# 17_PM8916_LDO.net
KiCad netlist of a schematic drawn in Altium Designer
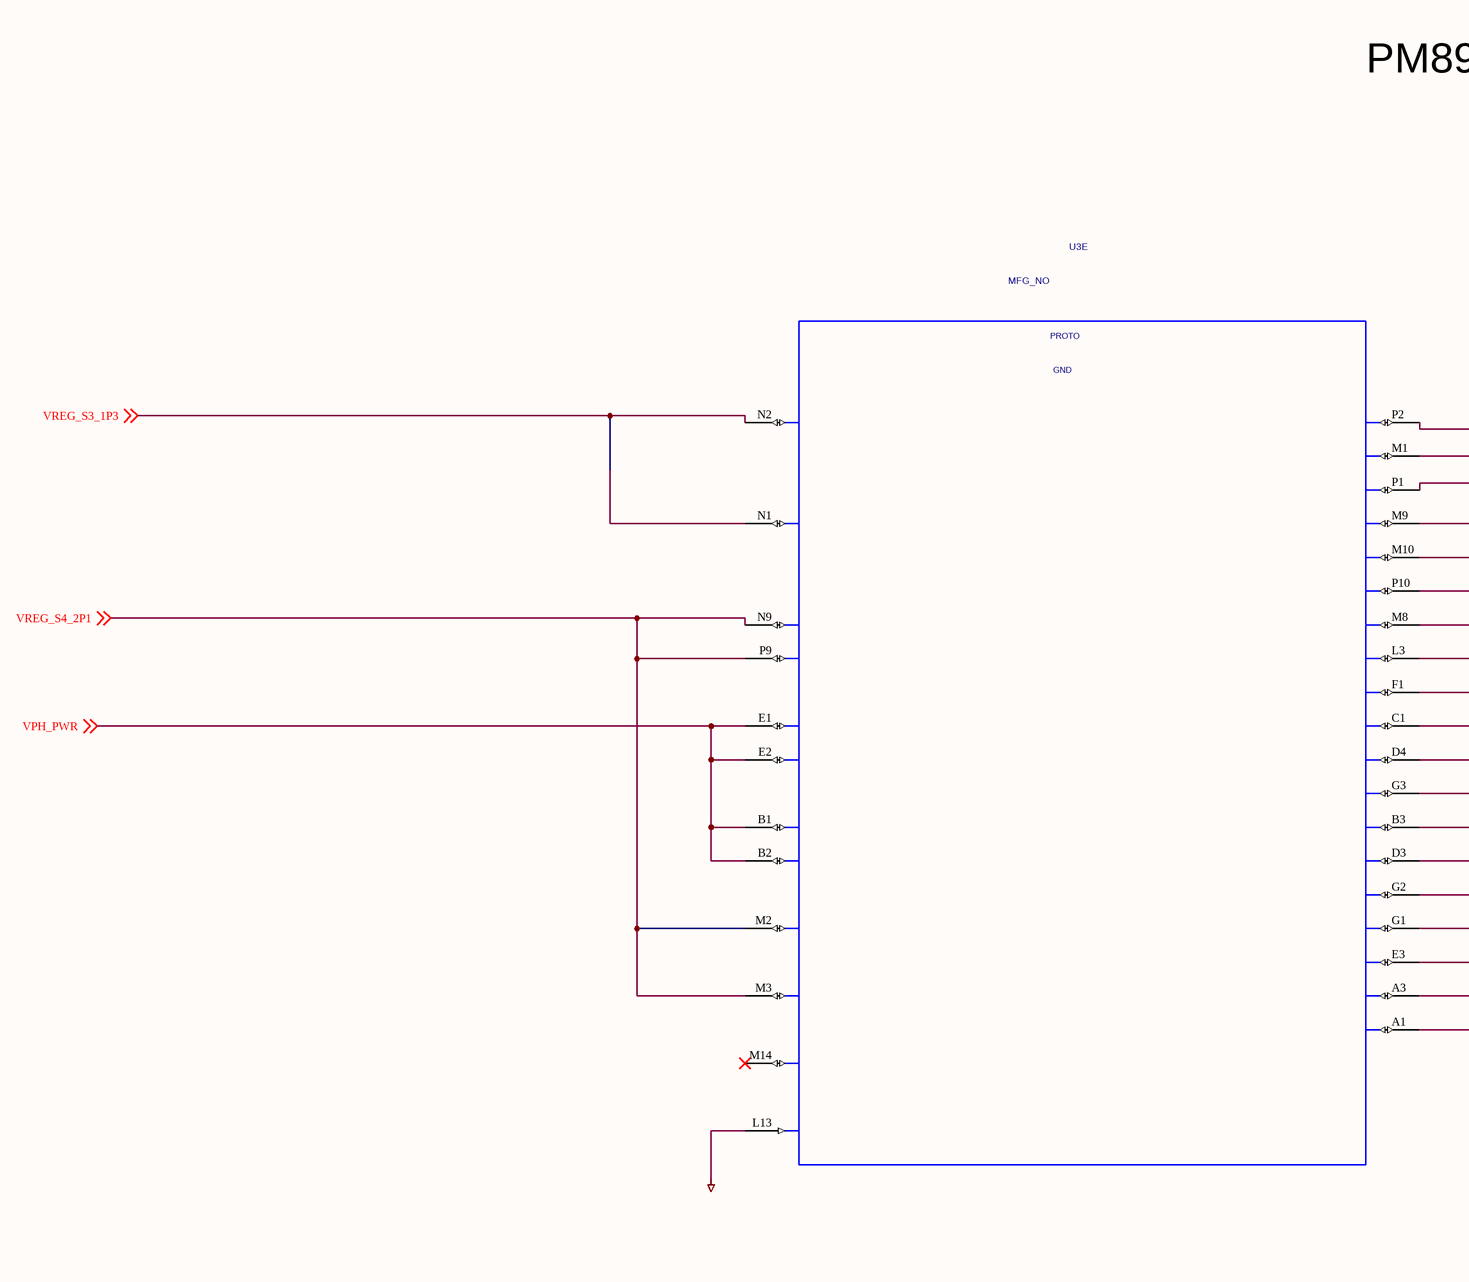
[diagram p0: 17 PM8916_LDO.SchDoc, top left]
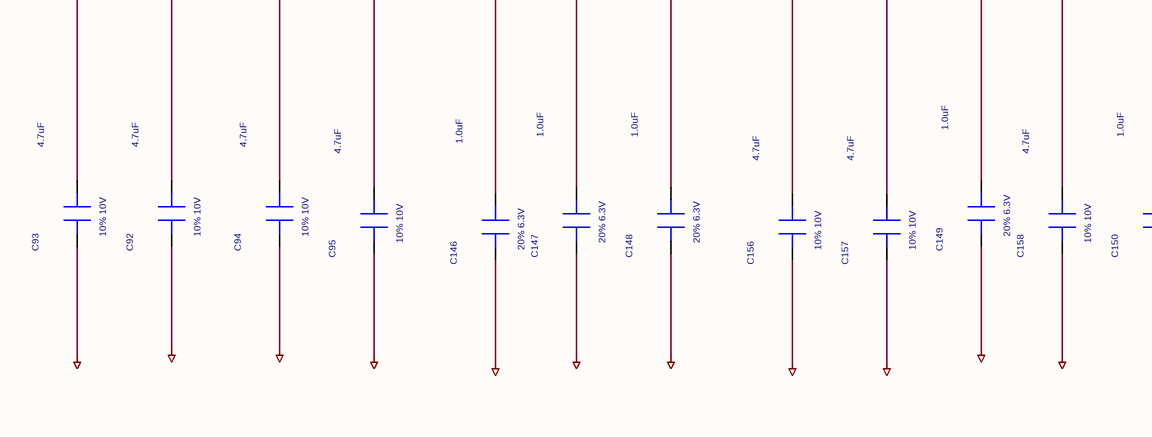
[diagram p1: 17 PM8916_LDO.SchDoc, top middle]
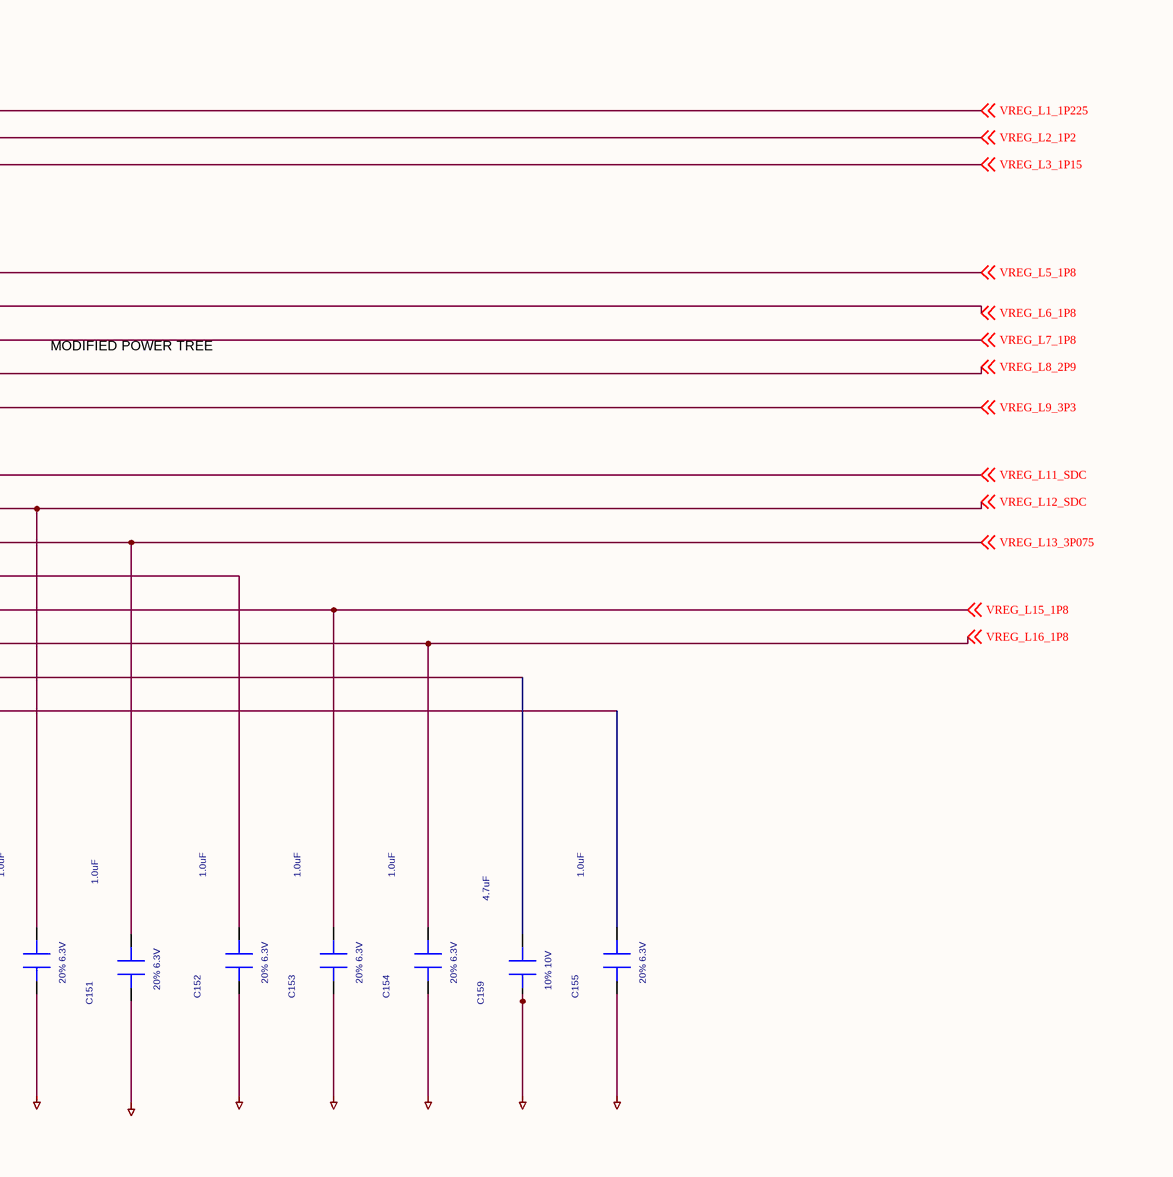
[diagram p2: 17 PM8916_LDO.SchDoc, top right]
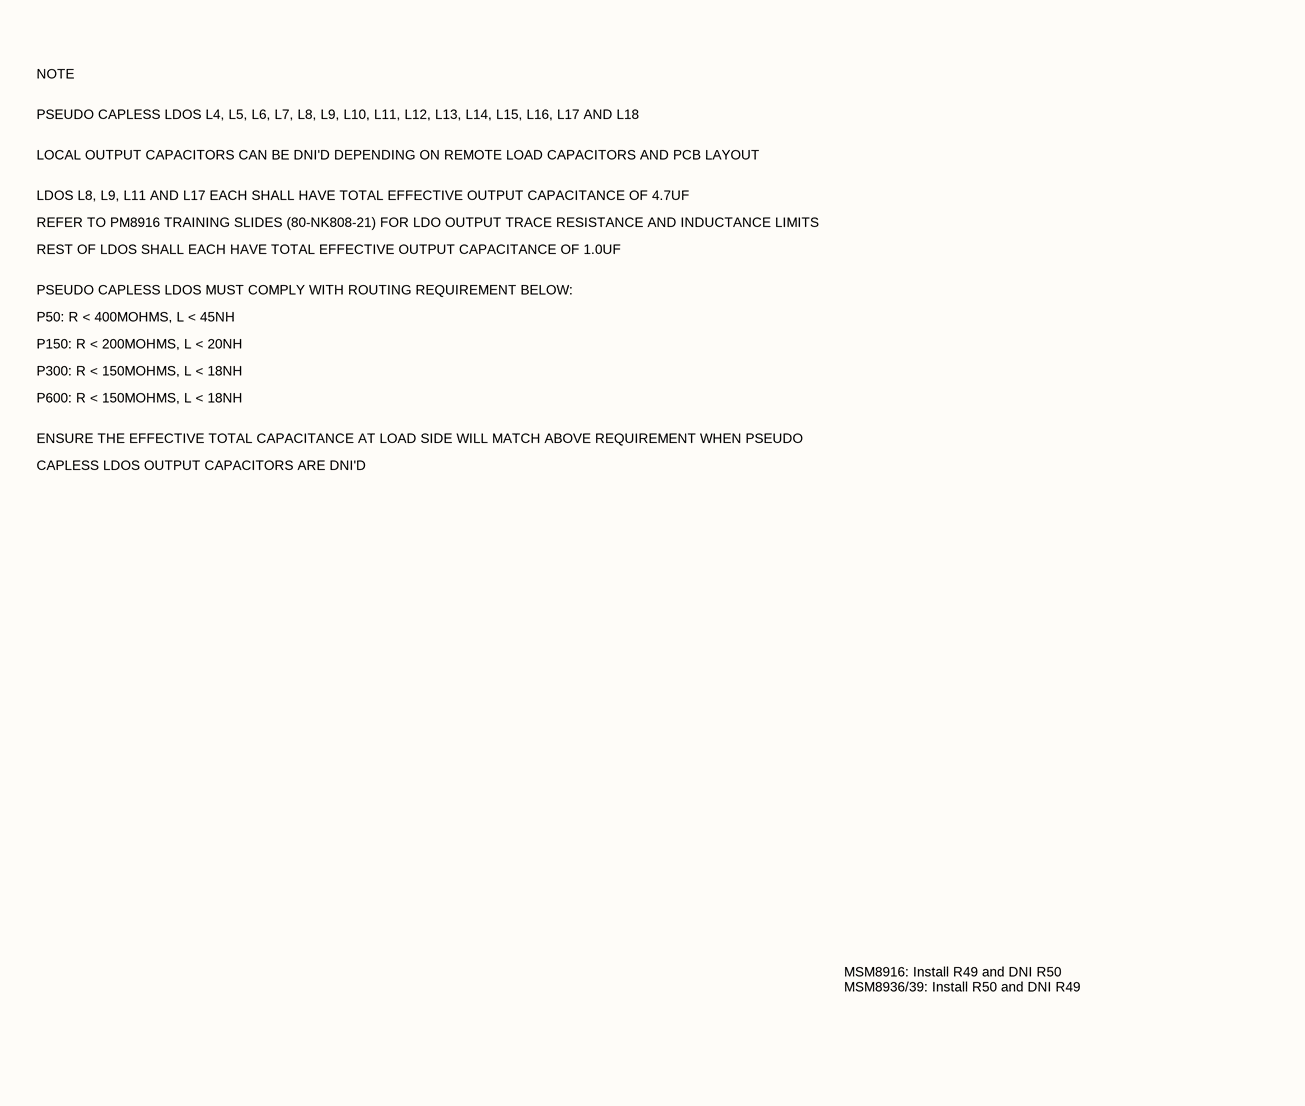
[diagram p3: 17 PM8916_LDO.SchDoc, bottom left]
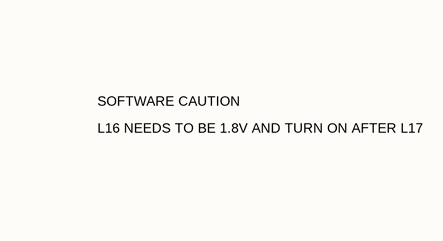
[diagram p4: 17 PM8916_LDO.SchDoc, bottom middle]
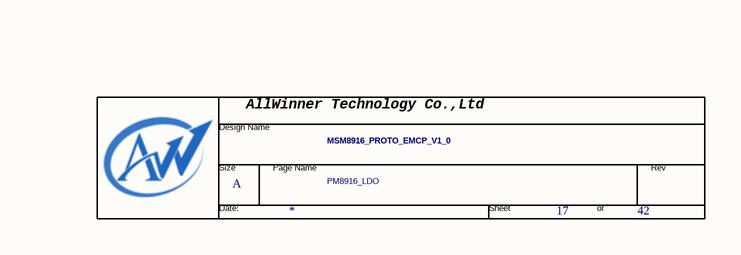
[diagram p5: 17 PM8916_LDO.SchDoc, bottom right]

(export (version "E")
  (design (tool "Eeschema 10.0.6"))
  (components
    (comp (ref "C92")
      (value "4.7uF")
      (footprint "c0402")
      (fields (field (name "TOLERANCE") "10% 10V") (field (name "PART_NUMBER") "MCN_NO"))
      (libsource (lib "MSM8916_DRAM_PMIC_REF_Library") (part "CAP#1"))
    )
    (comp (ref "C93")
      (value "4.7uF")
      (footprint "c0402")
      (fields (field (name "TOLERANCE") "10% 10V") (field (name "PART_NUMBER") "MCN_NO"))
      (libsource (lib "MSM8916_DRAM_PMIC_REF_Library") (part "CAP#1"))
    )
    (comp (ref "C94")
      (value "4.7uF")
      (footprint "c0402")
      (fields (field (name "TOLERANCE") "10% 10V") (field (name "PART_NUMBER") "MCN_NO"))
      (libsource (lib "MSM8916_DRAM_PMIC_REF_Library") (part "CAP#1"))
    )
    (comp (ref "C95")
      (value "4.7uF")
      (footprint "c0402")
      (fields (field (name "TOLERANCE") "10% 10V") (field (name "PART_NUMBER") "MCN_NO"))
      (libsource (lib "MSM8916_DRAM_PMIC_REF_Library") (part "CAP#1"))
    )
    (comp (ref "C146")
      (value "1.0uF")
      (footprint "c0402")
      (fields (field (name "TOLERANCE") "20% 6.3V") (field (name "PART_NUMBER") "MCN_NO"))
      (libsource (lib "MSM8916_DRAM_PMIC_REF_Library") (part "CAP#1"))
    )
    (comp (ref "C147")
      (value "1.0uF")
      (footprint "c0402")
      (fields (field (name "TOLERANCE") "20% 6.3V") (field (name "PART_NUMBER") "MCN_NO"))
      (libsource (lib "MSM8916_DRAM_PMIC_REF_Library") (part "CAP#1"))
    )
    (comp (ref "C148")
      (value "1.0uF")
      (footprint "c0402")
      (fields (field (name "TOLERANCE") "20% 6.3V") (field (name "PART_NUMBER") "MCN_NO"))
      (libsource (lib "MSM8916_DRAM_PMIC_REF_Library") (part "CAP#1"))
    )
    (comp (ref "C149")
      (value "1.0uF")
      (footprint "c0402")
      (fields (field (name "TOLERANCE") "20% 6.3V") (field (name "PART_NUMBER") "MCN_NO"))
      (libsource (lib "MSM8916_DRAM_PMIC_REF_Library") (part "CAP#1"))
    )
    (comp (ref "C150")
      (value "1.0uF")
      (footprint "c0402")
      (fields (field (name "TOLERANCE") "20% 6.3V") (field (name "PART_NUMBER") "MCN_NO"))
      (libsource (lib "MSM8916_DRAM_PMIC_REF_Library") (part "CAP#1"))
    )
    (comp (ref "C151")
      (value "1.0uF")
      (footprint "c0402")
      (fields (field (name "TOLERANCE") "20% 6.3V") (field (name "PART_NUMBER") "MCN_NO"))
      (libsource (lib "MSM8916_DRAM_PMIC_REF_Library") (part "CAP#1"))
    )
    (comp (ref "C152")
      (value "1.0uF")
      (footprint "c0402")
      (fields (field (name "TOLERANCE") "20% 6.3V") (field (name "PART_NUMBER") "MCN_NO"))
      (libsource (lib "MSM8916_DRAM_PMIC_REF_Library") (part "CAP#1"))
    )
    (comp (ref "C153")
      (value "1.0uF")
      (footprint "c0402")
      (fields (field (name "TOLERANCE") "20% 6.3V") (field (name "PART_NUMBER") "MCN_NO"))
      (libsource (lib "MSM8916_DRAM_PMIC_REF_Library") (part "CAP#1"))
    )
    (comp (ref "C154")
      (value "1.0uF")
      (footprint "c0402")
      (fields (field (name "TOLERANCE") "20% 6.3V") (field (name "PART_NUMBER") "MCN_NO"))
      (libsource (lib "MSM8916_DRAM_PMIC_REF_Library") (part "CAP#1"))
    )
    (comp (ref "C155")
      (value "1.0uF")
      (footprint "c0402")
      (fields (field (name "TOLERANCE") "20% 6.3V") (field (name "PART_NUMBER") "MCN_NO"))
      (libsource (lib "MSM8916_DRAM_PMIC_REF_Library") (part "CAP#1"))
    )
    (comp (ref "C156")
      (value "4.7uF")
      (footprint "c0402")
      (fields (field (name "TOLERANCE") "10% 10V") (field (name "PART_NUMBER") "MCN_NO"))
      (libsource (lib "MSM8916_DRAM_PMIC_REF_Library") (part "CAP#1"))
    )
    (comp (ref "C157")
      (value "4.7uF")
      (footprint "c0402")
      (fields (field (name "TOLERANCE") "10% 10V") (field (name "PART_NUMBER") "MCN_NO"))
      (libsource (lib "MSM8916_DRAM_PMIC_REF_Library") (part "CAP#1"))
    )
    (comp (ref "C158")
      (value "4.7uF")
      (footprint "c0402")
      (fields (field (name "TOLERANCE") "10% 10V") (field (name "PART_NUMBER") "MCN_NO"))
      (libsource (lib "MSM8916_DRAM_PMIC_REF_Library") (part "CAP#1"))
    )
    (comp (ref "C159")
      (value "4.7uF")
      (footprint "c0402")
      (fields (field (name "TOLERANCE") "10% 10V") (field (name "PART_NUMBER") "MCN_NO"))
      (libsource (lib "MSM8916_DRAM_PMIC_REF_Library") (part "CAP#1"))
    )
    (comp (ref "U3")
      (value "ASIC_PM8916")
      (footprint "PM-8916-0-176NSP-TR-00-0")
      (fields
        (field (name "SYMNAME") "GND")
        (field (name "PART_NUMBER") "MCN_NO")
        (field (name "PART_ID") "MFG_NO")
        (field (name "BLOCKID") "PROTO")
      )
      (libsource (lib "MSM8916_DRAM_PMIC_REF_Library") (part "ASIC_PM8916"))
    )
  )
  (nets
    (net (code "1") (name "DGND") (class "Default")
      (node (ref "C146") (pin "1") (pinfunction "POS_1") (pintype "bidirectional"))
      (node (ref "C147") (pin "1") (pinfunction "POS_1") (pintype "bidirectional"))
      (node (ref "C148") (pin "1") (pinfunction "POS_1") (pintype "bidirectional"))
      (node (ref "C149") (pin "1") (pinfunction "POS_1") (pintype "bidirectional"))
      (node (ref "C150") (pin "1") (pinfunction "POS_1") (pintype "bidirectional"))
      (node (ref "C151") (pin "1") (pinfunction "POS_1") (pintype "bidirectional"))
      (node (ref "C152") (pin "1") (pinfunction "POS_1") (pintype "bidirectional"))
      (node (ref "C153") (pin "1") (pinfunction "POS_1") (pintype "bidirectional"))
      (node (ref "C154") (pin "1") (pinfunction "POS_1") (pintype "bidirectional"))
      (node (ref "C155") (pin "1") (pinfunction "POS_1") (pintype "bidirectional"))
      (node (ref "C156") (pin "1") (pinfunction "POS_1") (pintype "bidirectional"))
      (node (ref "C157") (pin "1") (pinfunction "POS_1") (pintype "bidirectional"))
      (node (ref "C158") (pin "1") (pinfunction "POS_1") (pintype "bidirectional"))
      (node (ref "C159") (pin "1") (pinfunction "POS_1") (pintype "bidirectional"))
      (node (ref "C92") (pin "1") (pinfunction "POS_1") (pintype "bidirectional"))
      (node (ref "C93") (pin "1") (pinfunction "POS_1") (pintype "bidirectional"))
      (node (ref "C94") (pin "1") (pinfunction "POS_1") (pintype "bidirectional"))
      (node (ref "C95") (pin "1") (pinfunction "POS_1") (pintype "bidirectional"))
      (node (ref "U3") (pin "L13") (pinfunction "GND_DRV_L13") (pintype "input"))
    )
    (net (code "2") (name "Net-(C95-NEG)") (class "Default")
      (node (ref "C95") (pin "2") (pinfunction "NEG_2") (pintype "bidirectional"))
      (node (ref "U3") (pin "M10") (pinfunction "VREG_L4_2_M10") (pintype "bidirectional"))
      (node (ref "U3") (pin "M9") (pinfunction "VREG_L4_1_M9") (pintype "bidirectional"))
    )
    (net (code "3") (name "Net-(C149-NEG)") (class "Default")
      (node (ref "C149") (pin "2") (pinfunction "NEG_2") (pintype "bidirectional"))
      (node (ref "U3") (pin "D4") (pinfunction "VREG_L10_D4") (pintype "bidirectional"))
    )
    (net (code "4") (name "Net-(C152-NEG)") (class "Default")
      (node (ref "C152") (pin "2") (pinfunction "NEG_2") (pintype "bidirectional"))
      (node (ref "U3") (pin "G2") (pinfunction "VREG_L14_G2") (pintype "bidirectional"))
    )
    (net (code "5") (name "Net-(C155-NEG)") (class "Default")
      (node (ref "C155") (pin "2") (pinfunction "NEG_2") (pintype "bidirectional"))
      (node (ref "U3") (pin "A1") (pinfunction "VREG_L18_A1") (pintype "bidirectional"))
    )
    (net (code "6") (name "Net-(C159-NEG)") (class "Default")
      (node (ref "C159") (pin "2") (pinfunction "NEG_2") (pintype "bidirectional"))
      (node (ref "U3") (pin "A3") (pinfunction "VREG_L17_A3") (pintype "bidirectional"))
    )
    (net (code "7") (name "VPH_PWR") (class "Default")
      (node (ref "U3") (pin "B1") (pinfunction "VIN_GR5_A_B1") (pintype "bidirectional"))
      (node (ref "U3") (pin "B2") (pinfunction "VIN_GR5_B_B2") (pintype "bidirectional"))
      (node (ref "U3") (pin "E1") (pinfunction "VIN_GR4_A_E1") (pintype "bidirectional"))
      (node (ref "U3") (pin "E2") (pinfunction "VIN_GR4_B_E2") (pintype "bidirectional"))
    )
    (net (code "8") (name "VREG_L1_1P225") (class "Default")
      (node (ref "C93") (pin "2") (pinfunction "NEG_2") (pintype "bidirectional"))
      (node (ref "U3") (pin "P2") (pinfunction "VREG_L1_P2") (pintype "bidirectional"))
    )
    (net (code "9") (name "VREG_L2_1P2") (class "Default")
      (node (ref "C92") (pin "2") (pinfunction "NEG_2") (pintype "bidirectional"))
      (node (ref "U3") (pin "M1") (pinfunction "VREG_L2_M1") (pintype "bidirectional"))
    )
    (net (code "10") (name "VREG_L3_1P15") (class "Default")
      (node (ref "C94") (pin "2") (pinfunction "NEG_2") (pintype "bidirectional"))
      (node (ref "U3") (pin "P1") (pinfunction "VREG_L3_P1") (pintype "bidirectional"))
    )
    (net (code "11") (name "VREG_L5_1P8") (class "Default")
      (node (ref "C146") (pin "2") (pinfunction "NEG_2") (pintype "bidirectional"))
      (node (ref "U3") (pin "P10") (pinfunction "VREG_L5_P10") (pintype "bidirectional"))
    )
    (net (code "12") (name "VREG_L6_1P8") (class "Default")
      (node (ref "C147") (pin "2") (pinfunction "NEG_2") (pintype "bidirectional"))
      (node (ref "U3") (pin "M8") (pinfunction "VREG_L6_M8") (pintype "bidirectional"))
    )
    (net (code "13") (name "VREG_L7_1P8") (class "Default")
      (node (ref "C148") (pin "2") (pinfunction "NEG_2") (pintype "bidirectional"))
      (node (ref "U3") (pin "L3") (pinfunction "VREG_L7_L3") (pintype "bidirectional"))
    )
    (net (code "14") (name "VREG_L8_2P9") (class "Default")
      (node (ref "C156") (pin "2") (pinfunction "NEG_2") (pintype "bidirectional"))
      (node (ref "U3") (pin "F1") (pinfunction "VREG_L8_F1") (pintype "bidirectional"))
    )
    (net (code "15") (name "VREG_L9_3P3") (class "Default")
      (node (ref "C157") (pin "2") (pinfunction "NEG_2") (pintype "bidirectional"))
      (node (ref "U3") (pin "C1") (pinfunction "VREG_L9_C1") (pintype "bidirectional"))
    )
    (net (code "16") (name "VREG_L11_SDC") (class "Default")
      (node (ref "C158") (pin "2") (pinfunction "NEG_2") (pintype "bidirectional"))
      (node (ref "U3") (pin "G3") (pinfunction "VREG_L11_G3") (pintype "bidirectional"))
    )
    (net (code "17") (name "VREG_L12_SDC") (class "Default")
      (node (ref "C150") (pin "2") (pinfunction "NEG_2") (pintype "bidirectional"))
      (node (ref "U3") (pin "B3") (pinfunction "VREG_L12_B3") (pintype "bidirectional"))
    )
    (net (code "18") (name "VREG_L13_3P075") (class "Default")
      (node (ref "C151") (pin "2") (pinfunction "NEG_2") (pintype "bidirectional"))
      (node (ref "U3") (pin "D3") (pinfunction "VREG_L13_D3") (pintype "bidirectional"))
    )
    (net (code "19") (name "VREG_L15_1P8") (class "Default")
      (node (ref "C153") (pin "2") (pinfunction "NEG_2") (pintype "bidirectional"))
      (node (ref "U3") (pin "G1") (pinfunction "VREG_L15_G1") (pintype "bidirectional"))
    )
    (net (code "20") (name "VREG_L16_1P8") (class "Default")
      (node (ref "C154") (pin "2") (pinfunction "NEG_2") (pintype "bidirectional"))
      (node (ref "U3") (pin "E3") (pinfunction "VREG_L16_E3") (pintype "bidirectional"))
    )
    (net (code "21") (name "VREG_S3_1P3") (class "Default")
      (node (ref "U3") (pin "N1") (pinfunction "VIN_GR2_N1") (pintype "bidirectional"))
      (node (ref "U3") (pin "N2") (pinfunction "VIN_GR1_N2") (pintype "bidirectional"))
    )
    (net (code "22") (name "VREG_S4_2P1") (class "Default")
      (node (ref "U3") (pin "M2") (pinfunction "VIN_GR6_M2") (pintype "bidirectional"))
      (node (ref "U3") (pin "M3") (pinfunction "VIN_GR7_M3") (pintype "bidirectional"))
      (node (ref "U3") (pin "N9") (pinfunction "VIN_GR3_A_N9") (pintype "bidirectional"))
      (node (ref "U3") (pin "P9") (pinfunction "VIN_GR3_B_P9") (pintype "bidirectional"))
    )
    (net (code "23") (name "unconnected-(U3E-VIB_DRV*-PadM14)") (class "Default")
      (node (ref "U3") (pin "M14") (pinfunction "VIB_DRV*_M14") (pintype "bidirectional+no_connect"))
    )
  )
)
